# pcb_12v_stabiliser.net
KiCad netlist of a schematic drawn in EAGLE
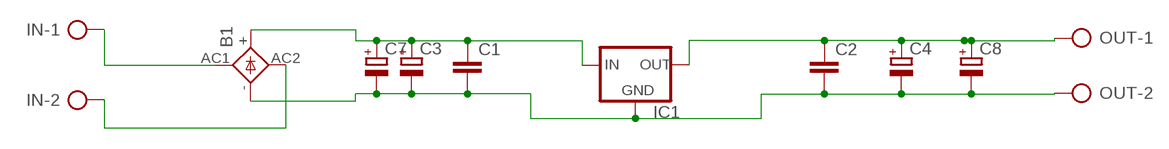
[diagram p0: schematic, sheet 1]

(export (version "E")
  (design (tool "Eeschema 10.0.6"))
  (components
    (comp (ref "B1")
      (value "2KBB-R")
      (footprint "eagle-import:2KBB-R")
      (libsource (lib "eagle-import") (part "2KBB-R"))
    )
    (comp (ref "C1")
      (value "C5/5")
      (footprint "eagle-import:C5B5")
      (libsource (lib "eagle-import") (part "C5/5"))
    )
    (comp (ref "C2")
      (value "C5/5")
      (footprint "eagle-import:C5B5")
      (libsource (lib "eagle-import") (part "C5/5"))
    )
    (comp (ref "C3")
      (value "CPOL-EUE5-8.5")
      (footprint "eagle-import:E5-8,5")
      (libsource (lib "eagle-import") (part "CPOL-EUE5-8.5"))
    )
    (comp (ref "C4")
      (value "CPOL-EUE5-8.5")
      (footprint "eagle-import:E5-8,5")
      (libsource (lib "eagle-import") (part "CPOL-EUE5-8.5"))
    )
    (comp (ref "C7")
      (value "CPOL-EUE5-10.5")
      (footprint "eagle-import:E5-10,5")
      (libsource (lib "eagle-import") (part "resistor_348_CPOL-EUE5-10.5"))
    )
    (comp (ref "C8")
      (value "CPOL-EUE5-10.5")
      (footprint "eagle-import:E5-10,5")
      (libsource (lib "eagle-import") (part "resistor_348_CPOL-EUE5-10.5"))
    )
    (comp (ref "IC1")
      (value "78XXS")
      (footprint "eagle-import:78XXS")
      (libsource (lib "eagle-import") (part "78XXS"))
    )
    (comp (ref "IN")
      (value "AK500/2-H")
      (footprint "eagle-import:AK500_2-H")
      (libsource (lib "eagle-import") (part "AK500/2-H"))
    )
    (comp (ref "OUT")
      (value "AK500/2-H")
      (footprint "eagle-import:AK500_2-H")
      (libsource (lib "eagle-import") (part "AK500/2-H"))
    )
  )
  (nets
    (net (code "1") (name "Net-(B1-Pad+)") (class "Default")
      (node (ref "B1") (pin "+") (pinfunction "+_+") (pintype "passive"))
      (node (ref "C1") (pin "1") (pinfunction "1_1") (pintype "passive"))
      (node (ref "C3") (pin "+") (pinfunction "+_+") (pintype "passive"))
      (node (ref "C7") (pin "+") (pinfunction "+_+") (pintype "passive"))
      (node (ref "IC1") (pin "IN") (pinfunction "IN_IN") (pintype "input"))
    )
    (net (code "2") (name "Net-(INA-KL)") (class "Default")
      (node (ref "B1") (pin "AC1") (pinfunction "AC1_AC1") (pintype "passive"))
      (node (ref "IN") (pin "1") (pinfunction "KL_1") (pintype "passive"))
    )
    (net (code "3") (name "Net-(INB-KL)") (class "Default")
      (node (ref "B1") (pin "AC2") (pinfunction "AC2_AC2") (pintype "passive"))
      (node (ref "IN") (pin "2") (pinfunction "KL_2") (pintype "passive"))
    )
    (net (code "4") (name "Net-(OUTA-KL)") (class "Default")
      (node (ref "C2") (pin "1") (pinfunction "1_1") (pintype "passive"))
      (node (ref "C4") (pin "+") (pinfunction "+_+") (pintype "passive"))
      (node (ref "C8") (pin "+") (pinfunction "+_+") (pintype "passive"))
      (node (ref "IC1") (pin "OUT") (pinfunction "OUT_OUT") (pintype "passive"))
      (node (ref "OUT") (pin "1") (pinfunction "KL_1") (pintype "passive"))
    )
    (net (code "5") (name "Net-(OUTB-KL)") (class "Default")
      (node (ref "B1") (pin "-") (pinfunction "-_-") (pintype "passive"))
      (node (ref "C1") (pin "2") (pinfunction "2_2") (pintype "passive"))
      (node (ref "C2") (pin "2") (pinfunction "2_2") (pintype "passive"))
      (node (ref "C3") (pin "-") (pinfunction "-_-") (pintype "passive"))
      (node (ref "C4") (pin "-") (pinfunction "-_-") (pintype "passive"))
      (node (ref "C7") (pin "-") (pinfunction "-_-") (pintype "passive"))
      (node (ref "C8") (pin "-") (pinfunction "-_-") (pintype "passive"))
      (node (ref "IC1") (pin "GND") (pinfunction "GND_GND") (pintype "input"))
      (node (ref "OUT") (pin "2") (pinfunction "KL_2") (pintype "passive"))
    )
  )
)
